# SW6124_A_B_C_MCU_LED.net
KiCad netlist of a schematic drawn in Altium Designer
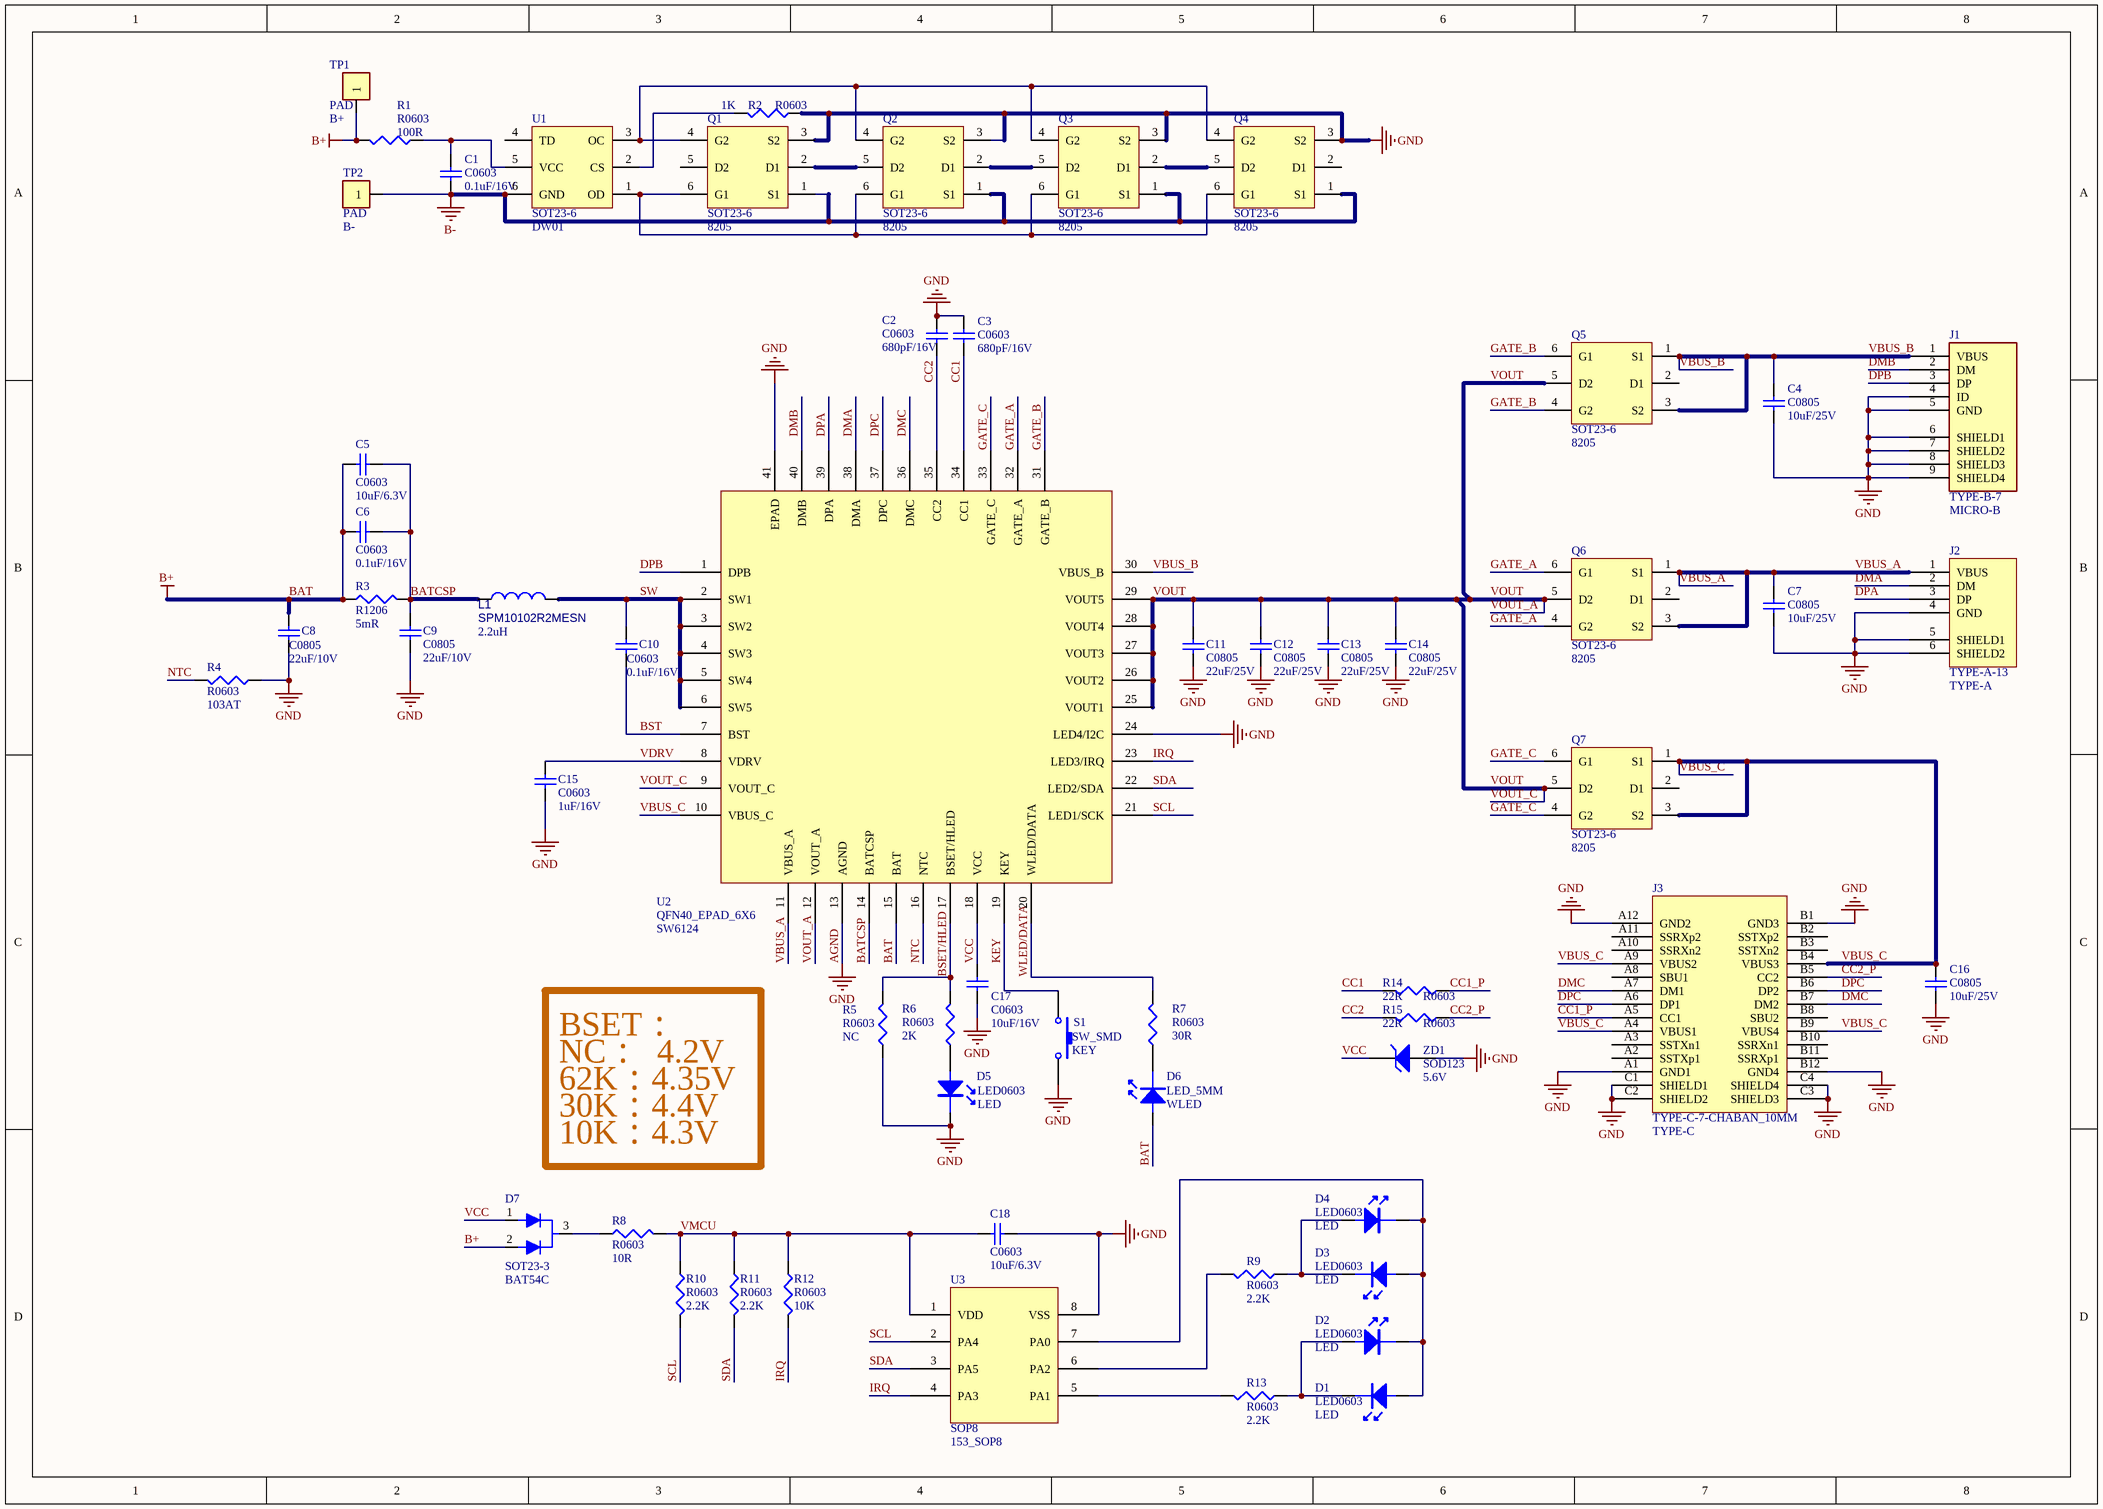
[diagram p0: SW6124+A+B+C+MCU+LED.SchDoc]

(export (version "E")
  (design (tool "Eeschema 10.0.6"))
  (components
    (comp (ref "C1")
      (value "C0603")
      (footprint "C0603")
      (description "Capacitor")
      (fields (field (name "ALTIUM_VALUE") "0.1uF/16V") (field (name "PUBLISHER") "Altium Limited"))
      (libsource (lib "*") (part "Cap"))
    )
    (comp (ref "C2")
      (value "C0603")
      (footprint "C0603")
      (description "Capacitor")
      (fields (field (name "ALTIUM_VALUE") "680pF/16V") (field (name "PUBLISHER") "Altium Limited"))
      (libsource (lib "*") (part "CAP0603"))
    )
    (comp (ref "C3")
      (value "C0603")
      (footprint "C0603")
      (description "Capacitor")
      (fields (field (name "ALTIUM_VALUE") "680pF/16V") (field (name "PUBLISHER") "Altium Limited"))
      (libsource (lib "*") (part "CAP0603"))
    )
    (comp (ref "C4")
      (value "C0805")
      (footprint "C0805")
      (description "Capacitor")
      (fields (field (name "ALTIUM_VALUE") "10uF/25V") (field (name "PUBLISHER") "Altium Limited"))
      (libsource (lib "*") (part "CAP0603"))
    )
    (comp (ref "C5")
      (value "C0603")
      (footprint "C0603")
      (description "Capacitor")
      (fields (field (name "ALTIUM_VALUE") "10uF/6.3V") (field (name "PUBLISHER") "Altium Limited"))
      (libsource (lib "*") (part "CAP0603"))
    )
    (comp (ref "C6")
      (value "C0603")
      (footprint "C0603")
      (description "Capacitor")
      (fields (field (name "ALTIUM_VALUE") "0.1uF/16V") (field (name "PUBLISHER") "Altium Limited"))
      (libsource (lib "*") (part "CAP0603"))
    )
    (comp (ref "C7")
      (value "C0805")
      (footprint "C0805")
      (description "Capacitor")
      (fields (field (name "ALTIUM_VALUE") "10uF/25V") (field (name "PUBLISHER") "Altium Limited"))
      (libsource (lib "*") (part "CAP0603"))
    )
    (comp (ref "C8")
      (value "C0805")
      (footprint "C0805")
      (description "Capacitor")
      (fields (field (name "ALTIUM_VALUE") "22uF/10V") (field (name "PUBLISHER") "Altium Limited"))
      (libsource (lib "*") (part "CAP0805"))
    )
    (comp (ref "C9")
      (value "C0805")
      (footprint "C0805")
      (description "Capacitor")
      (fields (field (name "ALTIUM_VALUE") "22uF/10V") (field (name "PUBLISHER") "Altium Limited"))
      (libsource (lib "*") (part "CAP0805"))
    )
    (comp (ref "C10")
      (value "C0603")
      (footprint "C0603")
      (description "Capacitor")
      (fields (field (name "ALTIUM_VALUE") "0.1uF/16V") (field (name "PUBLISHER") "Altium Limited"))
      (libsource (lib "*") (part "CAP0603"))
    )
    (comp (ref "C11")
      (value "C0805")
      (footprint "C0805")
      (description "Capacitor")
      (fields (field (name "ALTIUM_VALUE") "22uF/25V") (field (name "PUBLISHER") "Altium Limited"))
      (libsource (lib "*") (part "CAP0805"))
    )
    (comp (ref "C12")
      (value "C0805")
      (footprint "C0805")
      (description "Capacitor")
      (fields (field (name "ALTIUM_VALUE") "22uF/25V") (field (name "PUBLISHER") "Altium Limited"))
      (libsource (lib "*") (part "CAP0805"))
    )
    (comp (ref "C13")
      (value "C0805")
      (footprint "C0805")
      (description "Capacitor")
      (fields (field (name "ALTIUM_VALUE") "22uF/25V") (field (name "PUBLISHER") "Altium Limited"))
      (libsource (lib "*") (part "CAP0805"))
    )
    (comp (ref "C14")
      (value "C0805")
      (footprint "C0805")
      (description "Capacitor")
      (fields (field (name "ALTIUM_VALUE") "22uF/25V") (field (name "PUBLISHER") "Altium Limited"))
      (libsource (lib "*") (part "CAP0805"))
    )
    (comp (ref "C15")
      (value "C0603")
      (footprint "C0603")
      (description "Capacitor")
      (fields (field (name "ALTIUM_VALUE") "1uF/16V") (field (name "PUBLISHER") "Altium Limited"))
      (libsource (lib "*") (part "CAP0603"))
    )
    (comp (ref "C16")
      (value "C0805")
      (footprint "C0805")
      (description "Capacitor")
      (fields (field (name "ALTIUM_VALUE") "10uF/25V") (field (name "PUBLISHER") "Altium Limited"))
      (libsource (lib "*") (part "CAP0603"))
    )
    (comp (ref "C17")
      (value "C0603")
      (footprint "C0603")
      (description "Capacitor")
      (fields (field (name "ALTIUM_VALUE") "10uF/16V") (field (name "PUBLISHER") "Altium Limited"))
      (libsource (lib "*") (part "CAP0603"))
    )
    (comp (ref "C18")
      (value "C0603")
      (footprint "C0603")
      (description "Capacitor")
      (fields (field (name "ALTIUM_VALUE") "10uF/6.3V") (field (name "PUBLISHER") "Altium Limited"))
      (libsource (lib "*") (part "CAP0603"))
    )
    (comp (ref "D1") (value "LED") (footprint "LED0603") (libsource (lib "*") (part "LED")))
    (comp (ref "D2") (value "LED") (footprint "LED0603") (libsource (lib "*") (part "LED")))
    (comp (ref "D3") (value "LED") (footprint "LED0603") (libsource (lib "*") (part "LED")))
    (comp (ref "D4") (value "LED") (footprint "LED0603") (libsource (lib "*") (part "LED")))
    (comp (ref "D5") (value "LED") (footprint "LED0603") (libsource (lib "*") (part "LED")))
    (comp (ref "D6")
      (value "WLED")
      (footprint "LED_5MM")
      (fields (field (name "FOOTPRINF") "LED_5MM") (field (name "Comment") "LED_5MM"))
      (libsource (lib "*") (part "LED"))
    )
    (comp (ref "D7") (value "BAT54C") (footprint "SOT23-3") (libsource (lib "Schlib1-2012") (part "D3")))
    (comp (ref "J1")
      (value "MICRO-B")
      (footprint "TYPE-B-7")
      (fields (field (name "FOOTPRINTF") "TYPE-B-7") (field (name "Comment") "USB_MICRO_B"))
      (libsource (lib "*") (part "USB_MICRO_B"))
    )
    (comp (ref "J2")
      (value "TYPE-A")
      (footprint "TYPE-A-13")
      (fields (field (name "FOOTPRINF") "TYPE-A-13") (field (name "Comment") "TYPE-A-1"))
      (libsource (lib "*") (part "TYPE-A-1"))
    )
    (comp (ref "J3")
      (value "TYPE-C")
      (footprint "TYPE-C-7-CHABAN_10MM")
      (libsource (lib "*") (part "TYPE-C"))
    )
    (comp (ref "L1")
      (value "SPM10102R2MESN")
      (footprint "INDUCTOR_SPM1010")
      (fields (field (name "ALTIUM_VALUE") "2.2uH"))
      (libsource (lib "*") (part "INDUCTOR"))
    )
    (comp (ref "Q1")
      (value "8205")
      (footprint "SOT23-6")
      (fields (field (name "FOOTPRINF") "SOT23-6"))
      (libsource (lib "*") (part "8205B"))
    )
    (comp (ref "Q2")
      (value "8205")
      (footprint "SOT23-6")
      (fields (field (name "FOOTPRINF") "SOT23-6"))
      (libsource (lib "*") (part "8205B"))
    )
    (comp (ref "Q3")
      (value "8205")
      (footprint "SOT23-6")
      (fields (field (name "FOOTPRINF") "SOT23-6"))
      (libsource (lib "*") (part "8205B"))
    )
    (comp (ref "Q4")
      (value "8205")
      (footprint "SOT23-6")
      (fields (field (name "FOOTPRINF") "SOT23-6"))
      (libsource (lib "*") (part "8205B"))
    )
    (comp (ref "Q5")
      (value "8205")
      (footprint "SOT23-6")
      (fields (field (name "FOOTPRINF") "SOT23-6"))
      (libsource (lib "") (part "8205B_1"))
    )
    (comp (ref "Q6")
      (value "8205")
      (footprint "SOT23-6")
      (fields (field (name "FOOTPRINF") "SOT23-6"))
      (libsource (lib "") (part "8205B_1"))
    )
    (comp (ref "Q7")
      (value "8205")
      (footprint "SOT23-6")
      (fields (field (name "FOOTPRINF") "SOT23-6"))
      (libsource (lib "") (part "8205B_1"))
    )
    (comp (ref "R1")
      (value "R0603")
      (footprint "R0603")
      (description "Resistor")
      (fields (field (name "ALTIUM_VALUE") "100R") (field (name "PUBLISHER") "Altium Limited"))
      (libsource (lib "*") (part "Res3"))
    )
    (comp (ref "R2")
      (value "R0603")
      (footprint "R0603")
      (description "Resistor")
      (fields (field (name "ALTIUM_VALUE") "1K") (field (name "PUBLISHER") "Altium Limited"))
      (libsource (lib "*") (part "Res3"))
    )
    (comp (ref "R3")
      (value "R1206")
      (footprint "R1206")
      (description "Resistor")
      (fields (field (name "ALTIUM_VALUE") "5mR") (field (name "PUBLISHER") "Altium Limited"))
      (libsource (lib "*") (part "RES"))
    )
    (comp (ref "R4")
      (value "R0603")
      (footprint "R0603")
      (description "Resistor")
      (fields (field (name "ALTIUM_VALUE") "103AT") (field (name "PUBLISHER") "Altium Limited"))
      (libsource (lib "*") (part "RES"))
    )
    (comp (ref "R5")
      (value "R0603")
      (footprint "R0603")
      (description "Resistor")
      (fields (field (name "ALTIUM_VALUE") "NC") (field (name "PUBLISHER") "Altium Limited"))
      (libsource (lib "*") (part "RES"))
    )
    (comp (ref "R6")
      (value "R0603")
      (footprint "R0603")
      (description "Resistor")
      (fields (field (name "ALTIUM_VALUE") "2K") (field (name "PUBLISHER") "Altium Limited"))
      (libsource (lib "*") (part "RES"))
    )
    (comp (ref "R7")
      (value "R0603")
      (footprint "R0603")
      (description "Resistor")
      (fields (field (name "ALTIUM_VALUE") "30R") (field (name "PUBLISHER") "Altium Limited"))
      (libsource (lib "*") (part "RES"))
    )
    (comp (ref "R8")
      (value "R0603")
      (footprint "R0603")
      (description "Resistor")
      (fields (field (name "ALTIUM_VALUE") "10R") (field (name "PUBLISHER") "Altium Limited"))
      (libsource (lib "*") (part "RES"))
    )
    (comp (ref "R9")
      (value "R0603")
      (footprint "R0603")
      (description "Resistor")
      (fields (field (name "ALTIUM_VALUE") "2.2K") (field (name "PUBLISHER") "Altium Limited"))
      (libsource (lib "*") (part "RES"))
    )
    (comp (ref "R10")
      (value "R0603")
      (footprint "R0603")
      (description "Resistor")
      (fields (field (name "ALTIUM_VALUE") "2.2K") (field (name "PUBLISHER") "Altium Limited"))
      (libsource (lib "*") (part "RES"))
    )
    (comp (ref "R11")
      (value "R0603")
      (footprint "R0603")
      (description "Resistor")
      (fields (field (name "ALTIUM_VALUE") "2.2K") (field (name "PUBLISHER") "Altium Limited"))
      (libsource (lib "*") (part "RES"))
    )
    (comp (ref "R12")
      (value "R0603")
      (footprint "R0603")
      (description "Resistor")
      (fields (field (name "ALTIUM_VALUE") "10K") (field (name "PUBLISHER") "Altium Limited"))
      (libsource (lib "*") (part "RES"))
    )
    (comp (ref "R13")
      (value "R0603")
      (footprint "R0603")
      (description "Resistor")
      (fields (field (name "ALTIUM_VALUE") "2.2K") (field (name "PUBLISHER") "Altium Limited"))
      (libsource (lib "*") (part "RES"))
    )
    (comp (ref "R14")
      (value "R0603")
      (footprint "R0603")
      (description "Resistor")
      (fields (field (name "ALTIUM_VALUE") "22R") (field (name "PUBLISHER") "Altium Limited"))
      (libsource (lib "*") (part "RES"))
    )
    (comp (ref "R15")
      (value "R0603")
      (footprint "R0603")
      (description "Resistor")
      (fields (field (name "ALTIUM_VALUE") "22R") (field (name "PUBLISHER") "Altium Limited"))
      (libsource (lib "*") (part "RES"))
    )
    (comp (ref "S1")
      (value "KEY")
      (footprint "SW_SMD")
      (fields (field (name "FOOTPRINF") "SW_SMD"))
      (libsource (lib "*") (part "SW K"))
    )
    (comp (ref "TP1") (value "B+") (footprint "PAD") (libsource (lib "") (part "Test Point_1")))
    (comp (ref "TP2") (value "B-") (footprint "PAD") (libsource (lib "*") (part "Test Point")))
    (comp (ref "U1")
      (value "DW01")
      (footprint "SOT23-6")
      (fields (field (name "FOOTPRINF") "SOT23-6"))
      (libsource (lib "*") (part "DW01"))
    )
    (comp (ref "U2")
      (value "SW6124")
      (footprint "QFN40_EPAD_6X6")
      (libsource (lib "TEST") (part "SW6106_AFC"))
    )
    (comp (ref "U3") (value "153_SOP8") (footprint "SOP8") (libsource (lib "TEST") (part "153_SOP8")))
    (comp (ref "ZD1")
      (value "SOD123")
      (footprint "SOD-123")
      (description "Zener Diode")
      (fields (field (name "ALTIUM_UNNAMED_1") "5.6V"))
      (libsource (lib "Miscellaneous Devices") (part "D Zener"))
    )
  )
  (nets
    (net (code "1") (name "/BATCSP") (class "Default")
      (node (ref "C5") (pin "2") (pinfunction "2_2") (pintype "passive"))
      (node (ref "C6") (pin "2") (pinfunction "2_2") (pintype "passive"))
      (node (ref "C9") (pin "2") (pinfunction "2_2") (pintype "passive"))
      (node (ref "L1") (pin "1") (pinfunction "1_1") (pintype "passive"))
      (node (ref "R3") (pin "2") (pinfunction "2_2") (pintype "passive"))
      (node (ref "U2") (pin "14") (pinfunction "BATCSP_14") (pintype "passive"))
    )
    (net (code "2") (name "/BSET{slash}HLED") (class "Default")
      (node (ref "R5") (pin "2") (pinfunction "2_2") (pintype "passive"))
      (node (ref "R6") (pin "2") (pinfunction "2_2") (pintype "passive"))
      (node (ref "U2") (pin "17") (pinfunction "BSET/HLED_17") (pintype "passive"))
    )
    (net (code "3") (name "/BST") (class "Default")
      (node (ref "C10") (pin "1") (pinfunction "1_1") (pintype "passive"))
      (node (ref "U2") (pin "7") (pinfunction "BST_7") (pintype "passive"))
    )
    (net (code "4") (name "/CC1") (class "Default")
      (node (ref "C3") (pin "1") (pinfunction "1_1") (pintype "passive"))
      (node (ref "R14") (pin "2") (pinfunction "2_2") (pintype "passive"))
      (node (ref "U2") (pin "34") (pinfunction "CC1_34") (pintype "passive"))
    )
    (net (code "5") (name "/CC1_P") (class "Default")
      (node (ref "J3") (pin "A5") (pinfunction "CC1_A5") (pintype "passive"))
      (node (ref "R14") (pin "1") (pinfunction "1_1") (pintype "passive"))
    )
    (net (code "6") (name "/CC2") (class "Default")
      (node (ref "C2") (pin "1") (pinfunction "1_1") (pintype "passive"))
      (node (ref "R15") (pin "2") (pinfunction "2_2") (pintype "passive"))
      (node (ref "U2") (pin "35") (pinfunction "CC2_35") (pintype "passive"))
    )
    (net (code "7") (name "/CC2_P") (class "Default")
      (node (ref "J3") (pin "B5") (pinfunction "CC2_B5") (pintype "passive"))
      (node (ref "R15") (pin "1") (pinfunction "1_1") (pintype "passive"))
    )
    (net (code "8") (name "/DMA") (class "Default")
      (node (ref "J2") (pin "2") (pinfunction "DM_2") (pintype "passive"))
      (node (ref "U2") (pin "38") (pinfunction "DMA_38") (pintype "passive"))
    )
    (net (code "9") (name "/DMB") (class "Default")
      (node (ref "J1") (pin "2") (pinfunction "DM_2") (pintype "passive"))
      (node (ref "U2") (pin "40") (pinfunction "DMB_40") (pintype "passive"))
    )
    (net (code "10") (name "/DMC") (class "Default")
      (node (ref "J3") (pin "A7") (pinfunction "DM1_A7") (pintype "passive"))
      (node (ref "J3") (pin "B7") (pinfunction "DM2_B7") (pintype "passive"))
      (node (ref "U2") (pin "36") (pinfunction "DMC_36") (pintype "passive"))
    )
    (net (code "11") (name "/DPA") (class "Default")
      (node (ref "J2") (pin "3") (pinfunction "DP_3") (pintype "passive"))
      (node (ref "U2") (pin "39") (pinfunction "DPA_39") (pintype "passive"))
    )
    (net (code "12") (name "/DPB") (class "Default")
      (node (ref "J1") (pin "3") (pinfunction "DP_3") (pintype "passive"))
      (node (ref "U2") (pin "1") (pinfunction "DPB_1") (pintype "passive"))
    )
    (net (code "13") (name "/DPC") (class "Default")
      (node (ref "J3") (pin "A6") (pinfunction "DP1_A6") (pintype "passive"))
      (node (ref "J3") (pin "B6") (pinfunction "DP2_B6") (pintype "passive"))
      (node (ref "U2") (pin "37") (pinfunction "DPC_37") (pintype "passive"))
    )
    (net (code "14") (name "/GATE_A") (class "Default")
      (node (ref "Q6") (pin "4") (pinfunction "G2_4") (pintype "passive"))
      (node (ref "Q6") (pin "6") (pinfunction "G1_6") (pintype "passive"))
      (node (ref "U2") (pin "32") (pinfunction "GATE_A_32") (pintype "passive"))
    )
    (net (code "15") (name "/GATE_B") (class "Default")
      (node (ref "Q5") (pin "4") (pinfunction "G2_4") (pintype "passive"))
      (node (ref "Q5") (pin "6") (pinfunction "G1_6") (pintype "passive"))
      (node (ref "U2") (pin "31") (pinfunction "GATE_B_31") (pintype "passive"))
    )
    (net (code "16") (name "/GATE_C") (class "Default")
      (node (ref "Q7") (pin "4") (pinfunction "G2_4") (pintype "passive"))
      (node (ref "Q7") (pin "6") (pinfunction "G1_6") (pintype "passive"))
      (node (ref "U2") (pin "33") (pinfunction "GATE_C_33") (pintype "passive"))
    )
    (net (code "17") (name "/IRQ") (class "Default")
      (node (ref "R12") (pin "2") (pinfunction "2_2") (pintype "passive"))
      (node (ref "U2") (pin "23") (pinfunction "LED3/IRQ_23") (pintype "passive"))
      (node (ref "U3") (pin "4") (pinfunction "PA3_4") (pintype "passive"))
    )
    (net (code "18") (name "/KEY") (class "Default")
      (node (ref "S1") (pin "1") (pinfunction "1_1") (pintype "passive"))
      (node (ref "U2") (pin "19") (pinfunction "KEY_19") (pintype "passive"))
    )
    (net (code "19") (name "/NTC") (class "Default")
      (node (ref "R4") (pin "2") (pinfunction "2_2") (pintype "passive"))
      (node (ref "U2") (pin "16") (pinfunction "NTC_16") (pintype "passive"))
    )
    (net (code "20") (name "/SCL") (class "Default")
      (node (ref "R10") (pin "2") (pinfunction "2_2") (pintype "passive"))
      (node (ref "U2") (pin "21") (pinfunction "LED1/SCK_21") (pintype "passive"))
      (node (ref "U3") (pin "2") (pinfunction "PA4_2") (pintype "passive"))
    )
    (net (code "21") (name "/SDA") (class "Default")
      (node (ref "R11") (pin "2") (pinfunction "2_2") (pintype "passive"))
      (node (ref "U2") (pin "22") (pinfunction "LED2/SDA_22") (pintype "passive"))
      (node (ref "U3") (pin "3") (pinfunction "PA5_3") (pintype "passive"))
    )
    (net (code "22") (name "/SW") (class "Default")
      (node (ref "C10") (pin "2") (pinfunction "2_2") (pintype "passive"))
      (node (ref "L1") (pin "2") (pinfunction "2_2") (pintype "passive"))
      (node (ref "U2") (pin "2") (pinfunction "SW1_2") (pintype "passive"))
      (node (ref "U2") (pin "3") (pinfunction "SW2_3") (pintype "passive"))
      (node (ref "U2") (pin "4") (pinfunction "SW3_4") (pintype "passive"))
      (node (ref "U2") (pin "5") (pinfunction "SW4_5") (pintype "passive"))
      (node (ref "U2") (pin "6") (pinfunction "SW5_6") (pintype "passive"))
    )
    (net (code "23") (name "/VBUS_A") (class "Default")
      (node (ref "C7") (pin "2") (pinfunction "2_2") (pintype "passive"))
      (node (ref "J2") (pin "1") (pinfunction "VBUS_1") (pintype "passive"))
      (node (ref "Q6") (pin "1") (pinfunction "S1_1") (pintype "passive"))
      (node (ref "Q6") (pin "3") (pinfunction "S2_3") (pintype "passive"))
      (node (ref "U2") (pin "11") (pinfunction "VBUS_A_11") (pintype "passive"))
    )
    (net (code "24") (name "/VBUS_B") (class "Default")
      (node (ref "C4") (pin "2") (pinfunction "2_2") (pintype "passive"))
      (node (ref "J1") (pin "1") (pinfunction "VBUS_1") (pintype "passive"))
      (node (ref "Q5") (pin "1") (pinfunction "S1_1") (pintype "passive"))
      (node (ref "Q5") (pin "3") (pinfunction "S2_3") (pintype "passive"))
      (node (ref "U2") (pin "30") (pinfunction "VBUS_B_30") (pintype "passive"))
    )
    (net (code "25") (name "/VBUS_C") (class "Default")
      (node (ref "C16") (pin "2") (pinfunction "2_2") (pintype "passive"))
      (node (ref "J3") (pin "A4") (pinfunction "VBUS1_A4") (pintype "passive"))
      (node (ref "J3") (pin "A9") (pinfunction "VBUS2_A9") (pintype "passive"))
      (node (ref "J3") (pin "B4") (pinfunction "VBUS3_B4") (pintype "passive"))
      (node (ref "J3") (pin "B9") (pinfunction "VBUS4_B9") (pintype "passive"))
      (node (ref "Q7") (pin "1") (pinfunction "S1_1") (pintype "passive"))
      (node (ref "Q7") (pin "3") (pinfunction "S2_3") (pintype "passive"))
      (node (ref "U2") (pin "10") (pinfunction "VBUS_C_10") (pintype "passive"))
    )
    (net (code "26") (name "/VCC") (class "Default")
      (node (ref "C17") (pin "2") (pinfunction "2_2") (pintype "passive"))
      (node (ref "D7") (pin "1") (pintype "passive"))
      (node (ref "U2") (pin "18") (pinfunction "VCC_18") (pintype "passive"))
      (node (ref "ZD1") (pin "2") (pinfunction "K_2") (pintype "passive"))
    )
    (net (code "27") (name "/VDRV") (class "Default")
      (node (ref "C15") (pin "2") (pinfunction "2_2") (pintype "passive"))
      (node (ref "U2") (pin "8") (pinfunction "VDRV_8") (pintype "passive"))
    )
    (net (code "28") (name "/VMCU") (class "Default")
      (node (ref "C18") (pin "1") (pinfunction "1_1") (pintype "passive"))
      (node (ref "R10") (pin "1") (pinfunction "1_1") (pintype "passive"))
      (node (ref "R11") (pin "1") (pinfunction "1_1") (pintype "passive"))
      (node (ref "R12") (pin "1") (pinfunction "1_1") (pintype "passive"))
      (node (ref "R8") (pin "2") (pinfunction "2_2") (pintype "passive"))
      (node (ref "U3") (pin "1") (pinfunction "VDD_1") (pintype "passive"))
    )
    (net (code "29") (name "/VOUT") (class "Default")
      (node (ref "C11") (pin "2") (pinfunction "2_2") (pintype "passive"))
      (node (ref "C12") (pin "2") (pinfunction "2_2") (pintype "passive"))
      (node (ref "C13") (pin "2") (pinfunction "2_2") (pintype "passive"))
      (node (ref "C14") (pin "2") (pinfunction "2_2") (pintype "passive"))
      (node (ref "Q5") (pin "5") (pinfunction "D2_5") (pintype "passive"))
      (node (ref "Q6") (pin "5") (pinfunction "D2_5") (pintype "passive"))
      (node (ref "Q7") (pin "5") (pinfunction "D2_5") (pintype "passive"))
      (node (ref "U2") (pin "12") (pinfunction "VOUT_A_12") (pintype "passive"))
      (node (ref "U2") (pin "25") (pinfunction "VOUT1_25") (pintype "passive"))
      (node (ref "U2") (pin "26") (pinfunction "VOUT2_26") (pintype "passive"))
      (node (ref "U2") (pin "27") (pinfunction "VOUT3_27") (pintype "passive"))
      (node (ref "U2") (pin "28") (pinfunction "VOUT4_28") (pintype "passive"))
      (node (ref "U2") (pin "29") (pinfunction "VOUT5_29") (pintype "passive"))
      (node (ref "U2") (pin "9") (pinfunction "VOUT_C_9") (pintype "passive"))
    )
    (net (code "30") (name "/WLED{slash}DATA") (class "Default")
      (node (ref "R7") (pin "2") (pinfunction "2_2") (pintype "passive"))
      (node (ref "U2") (pin "20") (pinfunction "WLED/DATA_20") (pintype "passive"))
    )
    (net (code "31") (name "B+") (class "Default")
      (node (ref "C5") (pin "1") (pinfunction "1_1") (pintype "passive"))
      (node (ref "C6") (pin "1") (pinfunction "1_1") (pintype "passive"))
      (node (ref "C8") (pin "2") (pinfunction "2_2") (pintype "passive"))
      (node (ref "D6") (pin "1") (pinfunction "A_1") (pintype "passive"))
      (node (ref "D7") (pin "2") (pintype "passive"))
      (node (ref "R1") (pin "2") (pinfunction "2_2") (pintype "passive"))
      (node (ref "R3") (pin "1") (pinfunction "1_1") (pintype "passive"))
      (node (ref "TP1") (pin "1") (pinfunction "1_1") (pintype "passive"))
      (node (ref "U2") (pin "15") (pinfunction "BAT_15") (pintype "passive"))
    )
    (net (code "32") (name "B-") (class "Default")
      (node (ref "C1") (pin "1") (pinfunction "1_1") (pintype "passive"))
      (node (ref "Q1") (pin "1") (pinfunction "S1_1") (pintype "passive"))
      (node (ref "Q2") (pin "1") (pinfunction "S1_1") (pintype "passive"))
      (node (ref "Q3") (pin "1") (pinfunction "S1_1") (pintype "passive"))
      (node (ref "Q4") (pin "1") (pinfunction "S1_1") (pintype "passive"))
      (node (ref "TP2") (pin "1") (pinfunction "1_1") (pintype "passive"))
      (node (ref "U1") (pin "6") (pinfunction "GND_6") (pintype "passive"))
    )
    (net (code "33") (name "GND") (class "Default")
      (node (ref "C11") (pin "1") (pinfunction "1_1") (pintype "passive"))
      (node (ref "C12") (pin "1") (pinfunction "1_1") (pintype "passive"))
      (node (ref "C13") (pin "1") (pinfunction "1_1") (pintype "passive"))
      (node (ref "C14") (pin "1") (pinfunction "1_1") (pintype "passive"))
      (node (ref "C15") (pin "1") (pinfunction "1_1") (pintype "passive"))
      (node (ref "C16") (pin "1") (pinfunction "1_1") (pintype "passive"))
      (node (ref "C17") (pin "1") (pinfunction "1_1") (pintype "passive"))
      (node (ref "C18") (pin "2") (pinfunction "2_2") (pintype "passive"))
      (node (ref "C2") (pin "2") (pinfunction "2_2") (pintype "passive"))
      (node (ref "C3") (pin "2") (pinfunction "2_2") (pintype "passive"))
      (node (ref "C4") (pin "1") (pinfunction "1_1") (pintype "passive"))
      (node (ref "C7") (pin "1") (pinfunction "1_1") (pintype "passive"))
      (node (ref "C8") (pin "1") (pinfunction "1_1") (pintype "passive"))
      (node (ref "C9") (pin "1") (pinfunction "1_1") (pintype "passive"))
      (node (ref "D5") (pin "2") (pinfunction "K_2") (pintype "passive"))
      (node (ref "J1") (pin "4") (pinfunction "ID_4") (pintype "passive"))
      (node (ref "J1") (pin "5") (pinfunction "GND_5") (pintype "passive"))
      (node (ref "J1") (pin "6") (pinfunction "SHIELD1_6") (pintype "passive"))
      (node (ref "J1") (pin "7") (pinfunction "SHIELD2_7") (pintype "passive"))
      (node (ref "J1") (pin "8") (pinfunction "SHIELD3_8") (pintype "passive"))
      (node (ref "J1") (pin "9") (pinfunction "SHIELD4_9") (pintype "passive"))
      (node (ref "J2") (pin "4") (pinfunction "GND_4") (pintype "passive"))
      (node (ref "J2") (pin "5") (pinfunction "SHIELD1_5") (pintype "passive"))
      (node (ref "J2") (pin "6") (pinfunction "SHIELD2_6") (pintype "passive"))
      (node (ref "J3") (pin "A1") (pinfunction "GND1_A1") (pintype "passive"))
      (node (ref "J3") (pin "A12") (pinfunction "GND2_A12") (pintype "passive"))
      (node (ref "J3") (pin "B1") (pinfunction "GND3_B1") (pintype "passive"))
      (node (ref "J3") (pin "B12") (pinfunction "GND4_B12") (pintype "passive"))
      (node (ref "J3") (pin "C1") (pinfunction "SHIELD1_C1") (pintype "passive"))
      (node (ref "J3") (pin "C2") (pinfunction "SHIELD2_C2") (pintype "passive"))
      (node (ref "J3") (pin "C3") (pinfunction "SHIELD3_C3") (pintype "passive"))
      (node (ref "J3") (pin "C4") (pinfunction "SHIELD4_C4") (pintype "passive"))
      (node (ref "Q1") (pin "3") (pinfunction "S2_3") (pintype "passive"))
      (node (ref "Q2") (pin "3") (pinfunction "S2_3") (pintype "passive"))
      (node (ref "Q3") (pin "3") (pinfunction "S2_3") (pintype "passive"))
      (node (ref "Q4") (pin "3") (pinfunction "S2_3") (pintype "passive"))
      (node (ref "R2") (pin "1") (pinfunction "1_1") (pintype "passive"))
      (node (ref "R4") (pin "1") (pinfunction "1_1") (pintype "passive"))
      (node (ref "R5") (pin "1") (pinfunction "1_1") (pintype "passive"))
      (node (ref "S1") (pin "2") (pinfunction "2_2") (pintype "passive"))
      (node (ref "U2") (pin "13") (pinfunction "AGND_13") (pintype "passive"))
      (node (ref "U2") (pin "24") (pinfunction "LED4/I2C_24") (pintype "passive"))
      (node (ref "U2") (pin "41") (pinfunction "EPAD_41") (pintype "passive"))
      (node (ref "U3") (pin "8") (pinfunction "VSS_8") (pintype "passive"))
      (node (ref "ZD1") (pin "1") (pinfunction "A_1") (pintype "passive"))
    )
    (net (code "34") (name "Net-(D1-A)") (class "Default")
      (node (ref "D1") (pin "1") (pinfunction "A_1") (pintype "passive"))
      (node (ref "D2") (pin "2") (pinfunction "K_2") (pintype "passive"))
      (node (ref "D3") (pin "1") (pinfunction "A_1") (pintype "passive"))
      (node (ref "D4") (pin "2") (pinfunction "K_2") (pintype "passive"))
      (node (ref "U3") (pin "7") (pinfunction "PA0_7") (pintype "passive"))
    )
    (net (code "35") (name "Net-(D1-K)") (class "Default")
      (node (ref "D1") (pin "2") (pinfunction "K_2") (pintype "passive"))
      (node (ref "D2") (pin "1") (pinfunction "A_1") (pintype "passive"))
      (node (ref "R13") (pin "1") (pinfunction "1_1") (pintype "passive"))
    )
    (net (code "36") (name "Net-(D3-K)") (class "Default")
      (node (ref "D3") (pin "2") (pinfunction "K_2") (pintype "passive"))
      (node (ref "D4") (pin "1") (pinfunction "A_1") (pintype "passive"))
      (node (ref "R9") (pin "1") (pinfunction "1_1") (pintype "passive"))
    )
    (net (code "37") (name "Net-(D5-A)") (class "Default")
      (node (ref "D5") (pin "1") (pinfunction "A_1") (pintype "passive"))
      (node (ref "R6") (pin "1") (pinfunction "1_1") (pintype "passive"))
    )
    (net (code "38") (name "Net-(D6-K)") (class "Default")
      (node (ref "D6") (pin "2") (pinfunction "K_2") (pintype "passive"))
      (node (ref "R7") (pin "1") (pinfunction "1_1") (pintype "passive"))
    )
    (net (code "39") (name "Net-(D7-Pad3)") (class "Default")
      (node (ref "D7") (pin "3") (pintype "passive"))
      (node (ref "R8") (pin "1") (pinfunction "1_1") (pintype "passive"))
    )
    (net (code "40") (name "Net-(Q1-D1)") (class "Default")
      (node (ref "Q1") (pin "2") (pinfunction "D1_2") (pintype "passive"))
      (node (ref "Q2") (pin "5") (pinfunction "D2_5") (pintype "passive"))
    )
    (net (code "41") (name "Net-(Q1-G1)") (class "Default")
      (node (ref "Q1") (pin "6") (pinfunction "G1_6") (pintype "passive"))
      (node (ref "Q2") (pin "6") (pinfunction "G1_6") (pintype "passive"))
      (node (ref "Q3") (pin "6") (pinfunction "G1_6") (pintype "passive"))
      (node (ref "Q4") (pin "6") (pinfunction "G1_6") (pintype "passive"))
      (node (ref "U1") (pin "1") (pinfunction "OD_1") (pintype "passive"))
    )
    (net (code "42") (name "Net-(Q1-G2)") (class "Default")
      (node (ref "Q1") (pin "4") (pinfunction "G2_4") (pintype "passive"))
      (node (ref "Q2") (pin "4") (pinfunction "G2_4") (pintype "passive"))
      (node (ref "Q3") (pin "4") (pinfunction "G2_4") (pintype "passive"))
      (node (ref "Q4") (pin "4") (pinfunction "G2_4") (pintype "passive"))
      (node (ref "U1") (pin "3") (pinfunction "OC_3") (pintype "passive"))
    )
    (net (code "43") (name "Net-(Q2-D1)") (class "Default")
      (node (ref "Q2") (pin "2") (pinfunction "D1_2") (pintype "passive"))
      (node (ref "Q3") (pin "5") (pinfunction "D2_5") (pintype "passive"))
    )
    (net (code "44") (name "Net-(Q3-D1)") (class "Default")
      (node (ref "Q3") (pin "2") (pinfunction "D1_2") (pintype "passive"))
      (node (ref "Q4") (pin "5") (pinfunction "D2_5") (pintype "passive"))
    )
    (net (code "45") (name "Net-(U1-CS)") (class "Default")
      (node (ref "R2") (pin "2") (pinfunction "2_2") (pintype "passive"))
      (node (ref "U1") (pin "2") (pinfunction "CS_2") (pintype "passive"))
    )
    (net (code "46") (name "Net-(U1-VCC)") (class "Default")
      (node (ref "C1") (pin "2") (pinfunction "2_2") (pintype "passive"))
      (node (ref "R1") (pin "1") (pinfunction "1_1") (pintype "passive"))
      (node (ref "U1") (pin "5") (pinfunction "VCC_5") (pintype "passive"))
    )
    (net (code "47") (name "Net-(U3-PA1)") (class "Default")
      (node (ref "R13") (pin "2") (pinfunction "2_2") (pintype "passive"))
      (node (ref "U3") (pin "5") (pinfunction "PA1_5") (pintype "passive"))
    )
    (net (code "48") (name "Net-(U3-PA2)") (class "Default")
      (node (ref "R9") (pin "2") (pinfunction "2_2") (pintype "passive"))
      (node (ref "U3") (pin "6") (pinfunction "PA2_6") (pintype "passive"))
    )
    (net (code "49") (name "unconnected-(J3-SBU1-PadA8)") (class "Default")
      (node (ref "J3") (pin "A8") (pinfunction "SBU1_A8") (pintype "passive"))
    )
    (net (code "50") (name "unconnected-(J3-SBU2-PadB8)") (class "Default")
      (node (ref "J3") (pin "B8") (pinfunction "SBU2_B8") (pintype "passive"))
    )
    (net (code "51") (name "unconnected-(J3-SSRXn1-PadB10)") (class "Default")
      (node (ref "J3") (pin "B10") (pinfunction "SSRXn1_B10") (pintype "passive"))
    )
    (net (code "52") (name "unconnected-(J3-SSRXn2-PadA10)") (class "Default")
      (node (ref "J3") (pin "A10") (pinfunction "SSRXn2_A10") (pintype "passive"))
    )
    (net (code "53") (name "unconnected-(J3-SSRXp1-PadB11)") (class "Default")
      (node (ref "J3") (pin "B11") (pinfunction "SSRXp1_B11") (pintype "passive"))
    )
    (net (code "54") (name "unconnected-(J3-SSRXp2-PadA11)") (class "Default")
      (node (ref "J3") (pin "A11") (pinfunction "SSRXp2_A11") (pintype "passive"))
    )
    (net (code "55") (name "unconnected-(J3-SSTXn1-PadA3)") (class "Default")
      (node (ref "J3") (pin "A3") (pinfunction "SSTXn1_A3") (pintype "passive"))
    )
    (net (code "56") (name "unconnected-(J3-SSTXn2-PadB3)") (class "Default")
      (node (ref "J3") (pin "B3") (pinfunction "SSTXn2_B3") (pintype "passive"))
    )
    (net (code "57") (name "unconnected-(J3-SSTXp1-PadA2)") (class "Default")
      (node (ref "J3") (pin "A2") (pinfunction "SSTXp1_A2") (pintype "passive"))
    )
    (net (code "58") (name "unconnected-(J3-SSTXp2-PadB2)") (class "Default")
      (node (ref "J3") (pin "B2") (pinfunction "SSTXp2_B2") (pintype "passive"))
    )
    (net (code "59") (name "unconnected-(Q1-D2-Pad5)") (class "Default")
      (node (ref "Q1") (pin "5") (pinfunction "D2_5") (pintype "passive"))
    )
    (net (code "60") (name "unconnected-(Q4-D1-Pad2)") (class "Default")
      (node (ref "Q4") (pin "2") (pinfunction "D1_2") (pintype "passive"))
    )
    (net (code "61") (name "unconnected-(Q5-D1-Pad2)") (class "Default")
      (node (ref "Q5") (pin "2") (pinfunction "D1_2") (pintype "passive"))
    )
    (net (code "62") (name "unconnected-(Q6-D1-Pad2)") (class "Default")
      (node (ref "Q6") (pin "2") (pinfunction "D1_2") (pintype "passive"))
    )
    (net (code "63") (name "unconnected-(Q7-D1-Pad2)") (class "Default")
      (node (ref "Q7") (pin "2") (pinfunction "D1_2") (pintype "passive"))
    )
    (net (code "64") (name "unconnected-(U1-TD-Pad4)") (class "Default")
      (node (ref "U1") (pin "4") (pinfunction "TD_4") (pintype "passive"))
    )
  )
)
